# a2-display.net
KiCad netlist of a schematic drawn in EAGLE
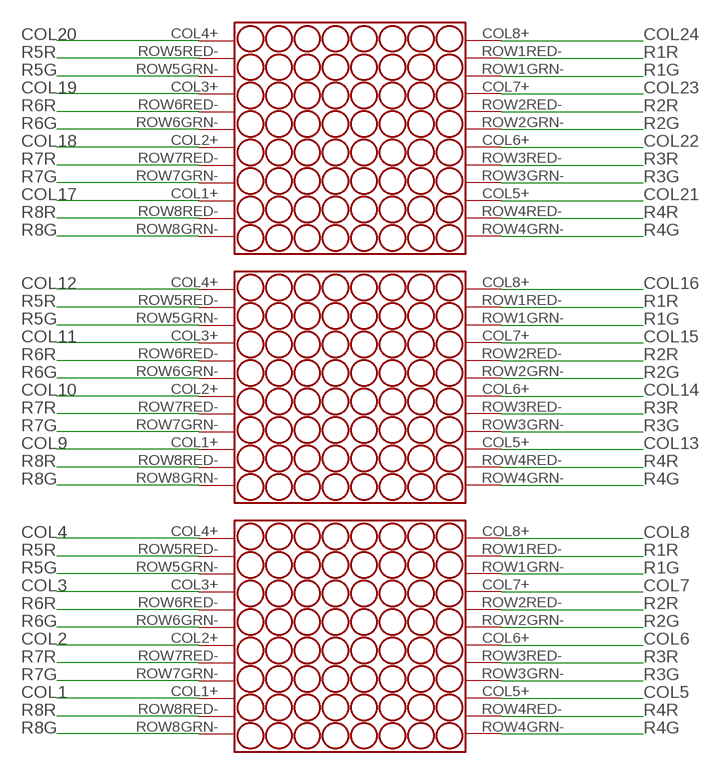
[diagram p0: schematic, sheet 1, part 1 of 2]
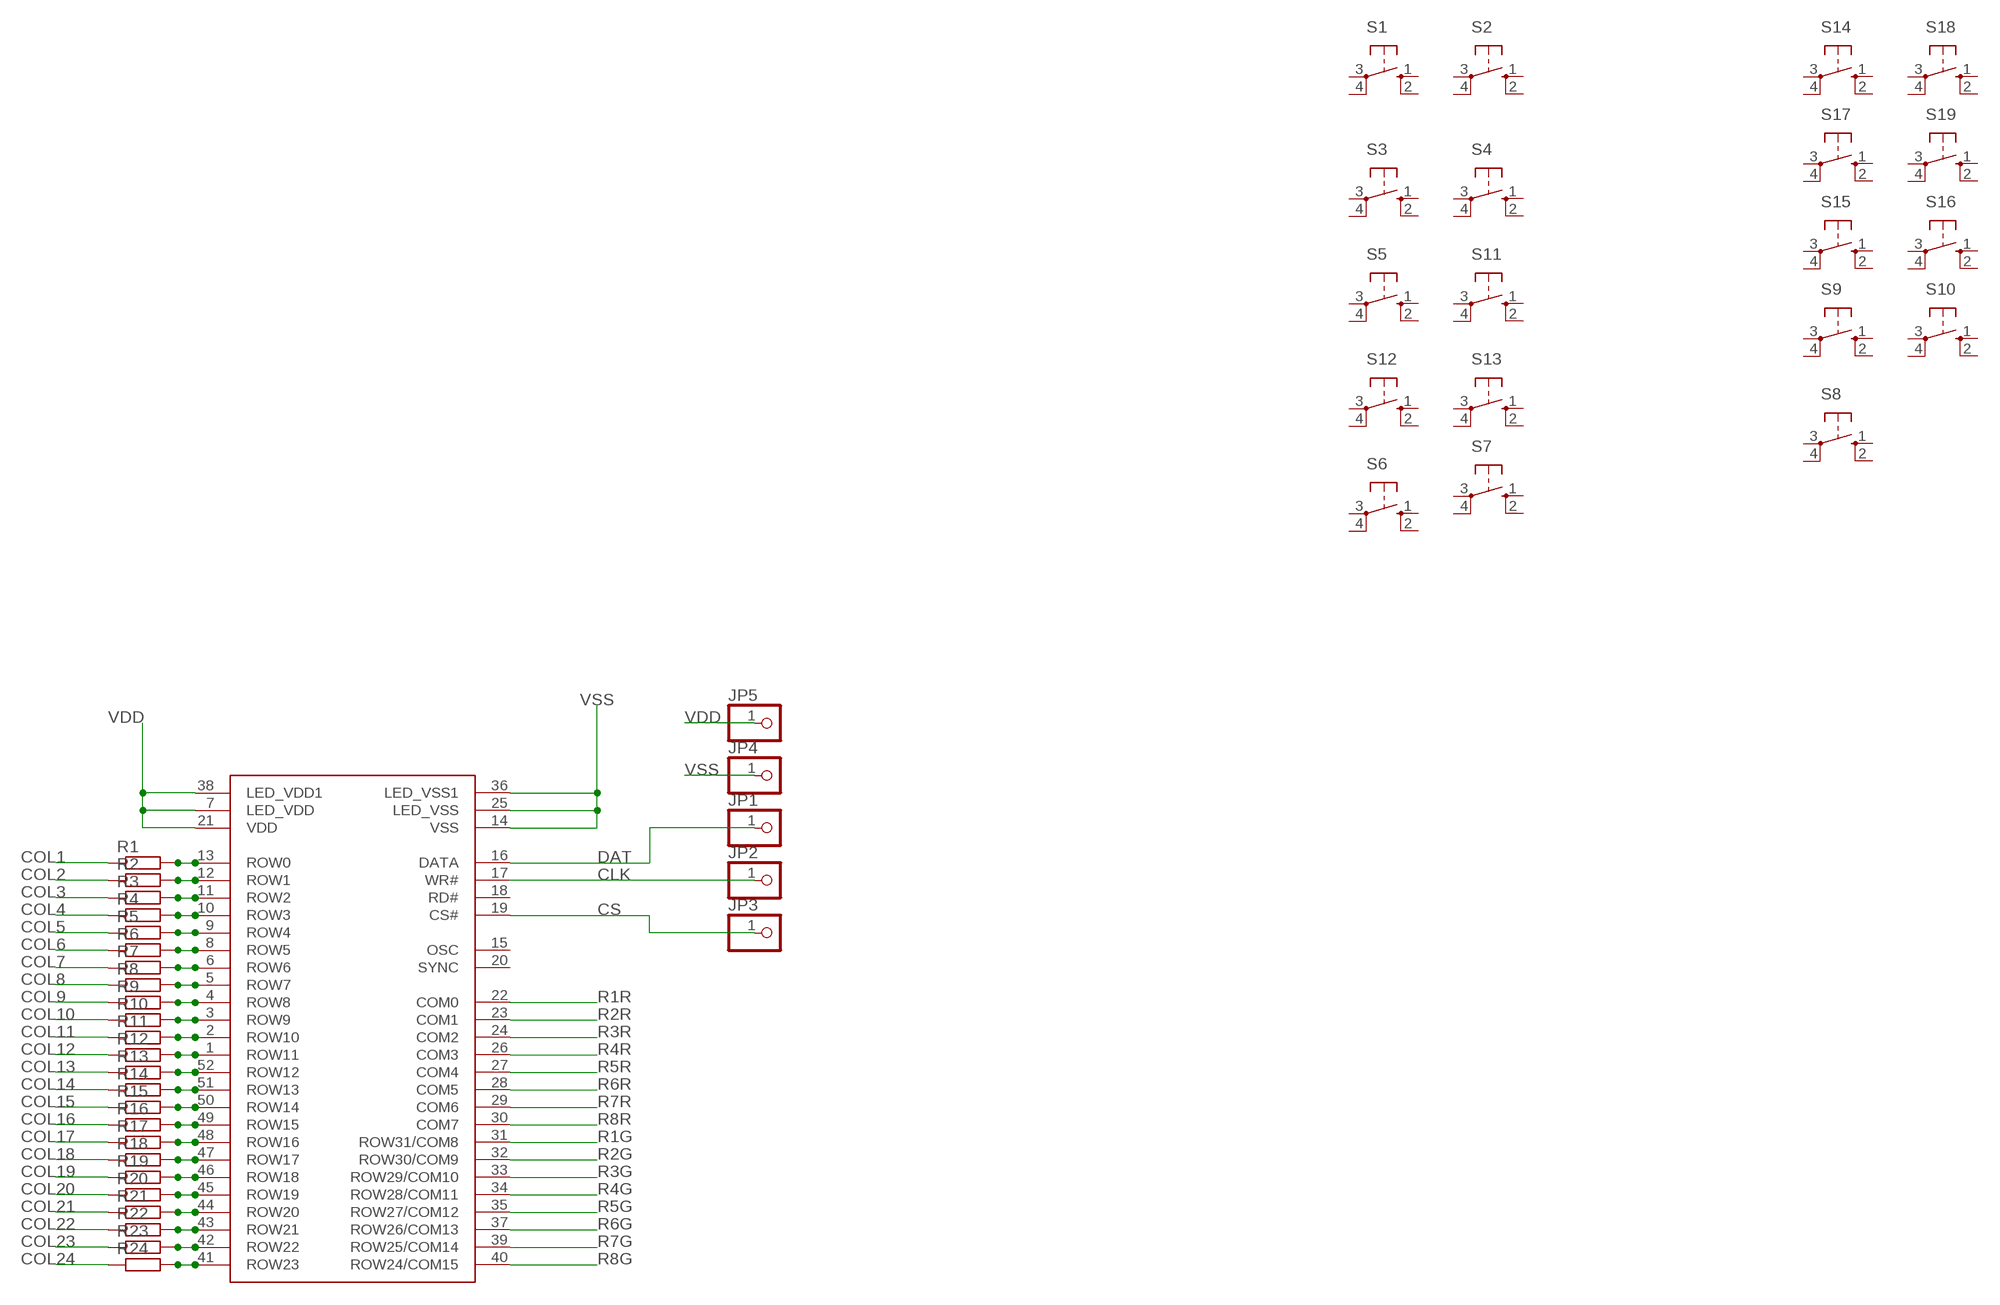
[diagram p1: schematic, sheet 1, part 2 of 2]

(export (version "E")
  (design (tool "Eeschema 10.0.6"))
  (components
    (comp (ref "IC1")
      (value "HT1632C")
      (footprint "eagle-import:QFP52")
      (libsource (lib "eagle-import") (part "HT1632C"))
    )
    (comp (ref "JP1")
      (value "PINHD-1X1")
      (footprint "eagle-import:1X01")
      (libsource (lib "eagle-import") (part "PINHD-1X1"))
    )
    (comp (ref "JP2")
      (value "PINHD-1X1")
      (footprint "eagle-import:1X01")
      (libsource (lib "eagle-import") (part "PINHD-1X1"))
    )
    (comp (ref "JP3")
      (value "PINHD-1X1")
      (footprint "eagle-import:1X01")
      (libsource (lib "eagle-import") (part "PINHD-1X1"))
    )
    (comp (ref "JP4")
      (value "PINHD-1X1")
      (footprint "eagle-import:1X01")
      (libsource (lib "eagle-import") (part "PINHD-1X1"))
    )
    (comp (ref "JP5")
      (value "PINHD-1X1")
      (footprint "eagle-import:1X01")
      (libsource (lib "eagle-import") (part "PINHD-1X1"))
    )
    (comp (ref "R1")
      (value "R-EU_R0805")
      (footprint "eagle-import:R0805")
      (libsource (lib "eagle-import") (part "R-EU_R0805"))
    )
    (comp (ref "R2")
      (value "R-EU_R0805")
      (footprint "eagle-import:R0805")
      (libsource (lib "eagle-import") (part "R-EU_R0805"))
    )
    (comp (ref "R3")
      (value "R-EU_R0805")
      (footprint "eagle-import:R0805")
      (libsource (lib "eagle-import") (part "R-EU_R0805"))
    )
    (comp (ref "R4")
      (value "R-EU_R0805")
      (footprint "eagle-import:R0805")
      (libsource (lib "eagle-import") (part "R-EU_R0805"))
    )
    (comp (ref "R5")
      (value "R-EU_R0805")
      (footprint "eagle-import:R0805")
      (libsource (lib "eagle-import") (part "R-EU_R0805"))
    )
    (comp (ref "R6")
      (value "R-EU_R0805")
      (footprint "eagle-import:R0805")
      (libsource (lib "eagle-import") (part "R-EU_R0805"))
    )
    (comp (ref "R7")
      (value "R-EU_R0805")
      (footprint "eagle-import:R0805")
      (libsource (lib "eagle-import") (part "R-EU_R0805"))
    )
    (comp (ref "R8")
      (value "R-EU_R0805")
      (footprint "eagle-import:R0805")
      (libsource (lib "eagle-import") (part "R-EU_R0805"))
    )
    (comp (ref "R9")
      (value "R-EU_R0805")
      (footprint "eagle-import:R0805")
      (libsource (lib "eagle-import") (part "R-EU_R0805"))
    )
    (comp (ref "R10")
      (value "R-EU_R0805")
      (footprint "eagle-import:R0805")
      (libsource (lib "eagle-import") (part "R-EU_R0805"))
    )
    (comp (ref "R11")
      (value "R-EU_R0805")
      (footprint "eagle-import:R0805")
      (libsource (lib "eagle-import") (part "R-EU_R0805"))
    )
    (comp (ref "R12")
      (value "R-EU_R0805")
      (footprint "eagle-import:R0805")
      (libsource (lib "eagle-import") (part "R-EU_R0805"))
    )
    (comp (ref "R13")
      (value "R-EU_R0805")
      (footprint "eagle-import:R0805")
      (libsource (lib "eagle-import") (part "R-EU_R0805"))
    )
    (comp (ref "R14")
      (value "R-EU_R0805")
      (footprint "eagle-import:R0805")
      (libsource (lib "eagle-import") (part "R-EU_R0805"))
    )
    (comp (ref "R15")
      (value "R-EU_R0805")
      (footprint "eagle-import:R0805")
      (libsource (lib "eagle-import") (part "R-EU_R0805"))
    )
    (comp (ref "R16")
      (value "R-EU_R0805")
      (footprint "eagle-import:R0805")
      (libsource (lib "eagle-import") (part "R-EU_R0805"))
    )
    (comp (ref "R17")
      (value "R-EU_R0805")
      (footprint "eagle-import:R0805")
      (libsource (lib "eagle-import") (part "R-EU_R0805"))
    )
    (comp (ref "R18")
      (value "R-EU_R0805")
      (footprint "eagle-import:R0805")
      (libsource (lib "eagle-import") (part "R-EU_R0805"))
    )
    (comp (ref "R19")
      (value "R-EU_R0805")
      (footprint "eagle-import:R0805")
      (libsource (lib "eagle-import") (part "R-EU_R0805"))
    )
    (comp (ref "R20")
      (value "R-EU_R0805")
      (footprint "eagle-import:R0805")
      (libsource (lib "eagle-import") (part "R-EU_R0805"))
    )
    (comp (ref "R21")
      (value "R-EU_R0805")
      (footprint "eagle-import:R0805")
      (libsource (lib "eagle-import") (part "R-EU_R0805"))
    )
    (comp (ref "R22")
      (value "R-EU_R0805")
      (footprint "eagle-import:R0805")
      (libsource (lib "eagle-import") (part "R-EU_R0805"))
    )
    (comp (ref "R23")
      (value "R-EU_R0805")
      (footprint "eagle-import:R0805")
      (libsource (lib "eagle-import") (part "R-EU_R0805"))
    )
    (comp (ref "R24")
      (value "R-EU_R0805")
      (footprint "eagle-import:R0805")
      (libsource (lib "eagle-import") (part "R-EU_R0805"))
    )
    (comp (ref "S1")
      (value "10-XX")
      (footprint "eagle-import:B3F-10XX")
      (fields (field (name "MPN") "B3F-1000"))
      (libsource (lib "eagle-import") (part "10-XX"))
    )
    (comp (ref "S2")
      (value "10-XX")
      (footprint "eagle-import:B3F-10XX")
      (fields (field (name "MPN") "B3F-1000"))
      (libsource (lib "eagle-import") (part "10-XX"))
    )
    (comp (ref "S3")
      (value "10-XX")
      (footprint "eagle-import:B3F-10XX")
      (fields (field (name "MPN") "B3F-1000"))
      (libsource (lib "eagle-import") (part "10-XX"))
    )
    (comp (ref "S4")
      (value "10-XX")
      (footprint "eagle-import:B3F-10XX")
      (fields (field (name "MPN") "B3F-1000"))
      (libsource (lib "eagle-import") (part "10-XX"))
    )
    (comp (ref "S5")
      (value "10-XX")
      (footprint "eagle-import:B3F-10XX")
      (fields (field (name "MPN") "B3F-1000"))
      (libsource (lib "eagle-import") (part "10-XX"))
    )
    (comp (ref "S6")
      (value "10-XX")
      (footprint "eagle-import:B3F-10XX")
      (fields (field (name "MPN") "B3F-1000"))
      (libsource (lib "eagle-import") (part "10-XX"))
    )
    (comp (ref "S7")
      (value "10-XX")
      (footprint "eagle-import:B3F-10XX")
      (fields (field (name "MPN") "B3F-1000"))
      (libsource (lib "eagle-import") (part "10-XX"))
    )
    (comp (ref "S8")
      (value "10-XX")
      (footprint "eagle-import:B3F-10XX")
      (fields (field (name "MPN") "B3F-1000"))
      (libsource (lib "eagle-import") (part "10-XX"))
    )
    (comp (ref "S9")
      (value "10-XX")
      (footprint "eagle-import:B3F-10XX")
      (fields (field (name "MPN") "B3F-1000"))
      (libsource (lib "eagle-import") (part "10-XX"))
    )
    (comp (ref "S10")
      (value "10-XX")
      (footprint "eagle-import:B3F-10XX")
      (fields (field (name "MPN") "B3F-1000"))
      (libsource (lib "eagle-import") (part "10-XX"))
    )
    (comp (ref "S11")
      (value "10-XX")
      (footprint "eagle-import:B3F-10XX")
      (fields (field (name "MPN") "B3F-1000"))
      (libsource (lib "eagle-import") (part "10-XX"))
    )
    (comp (ref "S12")
      (value "10-XX")
      (footprint "eagle-import:B3F-10XX")
      (fields (field (name "MPN") "B3F-1000"))
      (libsource (lib "eagle-import") (part "10-XX"))
    )
    (comp (ref "S13")
      (value "10-XX")
      (footprint "eagle-import:B3F-10XX")
      (fields (field (name "MPN") "B3F-1000"))
      (libsource (lib "eagle-import") (part "10-XX"))
    )
    (comp (ref "S14")
      (value "10-XX")
      (footprint "eagle-import:B3F-10XX")
      (fields (field (name "MPN") "B3F-1000"))
      (libsource (lib "eagle-import") (part "10-XX"))
    )
    (comp (ref "S15")
      (value "10-XX")
      (footprint "eagle-import:B3F-10XX")
      (fields (field (name "MPN") "B3F-1000"))
      (libsource (lib "eagle-import") (part "10-XX"))
    )
    (comp (ref "S16")
      (value "10-XX")
      (footprint "eagle-import:B3F-10XX")
      (fields (field (name "MPN") "B3F-1000"))
      (libsource (lib "eagle-import") (part "10-XX"))
    )
    (comp (ref "S17")
      (value "10-XX")
      (footprint "eagle-import:B3F-10XX")
      (fields (field (name "MPN") "B3F-1000"))
      (libsource (lib "eagle-import") (part "10-XX"))
    )
    (comp (ref "S18")
      (value "10-XX")
      (footprint "eagle-import:B3F-10XX")
      (fields (field (name "MPN") "B3F-1000"))
      (libsource (lib "eagle-import") (part "10-XX"))
    )
    (comp (ref "S19")
      (value "10-XX")
      (footprint "eagle-import:B3F-10XX")
      (fields (field (name "MPN") "B3F-1000"))
      (libsource (lib "eagle-import") (part "10-XX"))
    )
    (comp (ref "U$1")
      (value "8X8")
      (footprint "eagle-import:SURE8X8")
      (libsource (lib "eagle-import") (part "8X8"))
    )
    (comp (ref "U$2")
      (value "8X8")
      (footprint "eagle-import:SURE8X8")
      (libsource (lib "eagle-import") (part "8X8"))
    )
    (comp (ref "U$3")
      (value "8X8")
      (footprint "eagle-import:SURE8X8")
      (libsource (lib "eagle-import") (part "8X8"))
    )
  )
  (nets
    (net (code "1") (name "/CLK") (class "Default")
      (node (ref "IC1") (pin "17") (pinfunction "WR#_17") (pintype "bidirectional"))
      (node (ref "JP2") (pin "1") (pinfunction "1_1") (pintype "passive"))
    )
    (net (code "2") (name "/COL1") (class "Default")
      (node (ref "R1") (pin "1") (pinfunction "1_1") (pintype "passive"))
      (node (ref "U$3") (pin "COL1+") (pinfunction "COL1_AN_COL1+") (pintype "passive"))
    )
    (net (code "3") (name "/COL2") (class "Default")
      (node (ref "R2") (pin "1") (pinfunction "1_1") (pintype "passive"))
      (node (ref "U$3") (pin "COL2+") (pinfunction "COL2_AN_COL2+") (pintype "passive"))
    )
    (net (code "4") (name "/COL3") (class "Default")
      (node (ref "R3") (pin "1") (pinfunction "1_1") (pintype "passive"))
      (node (ref "U$3") (pin "COL3+") (pinfunction "COL3_AN_COL3+") (pintype "passive"))
    )
    (net (code "5") (name "/COL4") (class "Default")
      (node (ref "R4") (pin "1") (pinfunction "1_1") (pintype "passive"))
      (node (ref "U$3") (pin "COL4+") (pinfunction "COL4_AN_COL4+") (pintype "passive"))
    )
    (net (code "6") (name "/COL5") (class "Default")
      (node (ref "R5") (pin "1") (pinfunction "1_1") (pintype "passive"))
      (node (ref "U$3") (pin "COL5+") (pinfunction "COL5_AN_COL5+") (pintype "passive"))
    )
    (net (code "7") (name "/COL6") (class "Default")
      (node (ref "R6") (pin "1") (pinfunction "1_1") (pintype "passive"))
      (node (ref "U$3") (pin "COL6+") (pinfunction "COL6_AN_COL6+") (pintype "passive"))
    )
    (net (code "8") (name "/COL7") (class "Default")
      (node (ref "R7") (pin "1") (pinfunction "1_1") (pintype "passive"))
      (node (ref "U$3") (pin "COL7+") (pinfunction "COL7_AN_COL7+") (pintype "passive"))
    )
    (net (code "9") (name "/COL8") (class "Default")
      (node (ref "R8") (pin "1") (pinfunction "1_1") (pintype "passive"))
      (node (ref "U$3") (pin "COL8+") (pinfunction "COL8_AN_COL8+") (pintype "passive"))
    )
    (net (code "10") (name "/COL9") (class "Default")
      (node (ref "R9") (pin "1") (pinfunction "1_1") (pintype "passive"))
      (node (ref "U$2") (pin "COL1+") (pinfunction "COL1_AN_COL1+") (pintype "passive"))
    )
    (net (code "11") (name "/COL10") (class "Default")
      (node (ref "R10") (pin "1") (pinfunction "1_1") (pintype "passive"))
      (node (ref "U$2") (pin "COL2+") (pinfunction "COL2_AN_COL2+") (pintype "passive"))
    )
    (net (code "12") (name "/COL11") (class "Default")
      (node (ref "R11") (pin "1") (pinfunction "1_1") (pintype "passive"))
      (node (ref "U$2") (pin "COL3+") (pinfunction "COL3_AN_COL3+") (pintype "passive"))
    )
    (net (code "13") (name "/COL12") (class "Default")
      (node (ref "R12") (pin "1") (pinfunction "1_1") (pintype "passive"))
      (node (ref "U$2") (pin "COL4+") (pinfunction "COL4_AN_COL4+") (pintype "passive"))
    )
    (net (code "14") (name "/COL13") (class "Default")
      (node (ref "R13") (pin "1") (pinfunction "1_1") (pintype "passive"))
      (node (ref "U$2") (pin "COL5+") (pinfunction "COL5_AN_COL5+") (pintype "passive"))
    )
    (net (code "15") (name "/COL14") (class "Default")
      (node (ref "R14") (pin "1") (pinfunction "1_1") (pintype "passive"))
      (node (ref "U$2") (pin "COL6+") (pinfunction "COL6_AN_COL6+") (pintype "passive"))
    )
    (net (code "16") (name "/COL15") (class "Default")
      (node (ref "R15") (pin "1") (pinfunction "1_1") (pintype "passive"))
      (node (ref "U$2") (pin "COL7+") (pinfunction "COL7_AN_COL7+") (pintype "passive"))
    )
    (net (code "17") (name "/COL16") (class "Default")
      (node (ref "R16") (pin "1") (pinfunction "1_1") (pintype "passive"))
      (node (ref "U$2") (pin "COL8+") (pinfunction "COL8_AN_COL8+") (pintype "passive"))
    )
    (net (code "18") (name "/COL17") (class "Default")
      (node (ref "R17") (pin "1") (pinfunction "1_1") (pintype "passive"))
      (node (ref "U$1") (pin "COL1+") (pinfunction "COL1_AN_COL1+") (pintype "passive"))
    )
    (net (code "19") (name "/COL18") (class "Default")
      (node (ref "R18") (pin "1") (pinfunction "1_1") (pintype "passive"))
      (node (ref "U$1") (pin "COL2+") (pinfunction "COL2_AN_COL2+") (pintype "passive"))
    )
    (net (code "20") (name "/COL19") (class "Default")
      (node (ref "R19") (pin "1") (pinfunction "1_1") (pintype "passive"))
      (node (ref "U$1") (pin "COL3+") (pinfunction "COL3_AN_COL3+") (pintype "passive"))
    )
    (net (code "21") (name "/COL20") (class "Default")
      (node (ref "R20") (pin "1") (pinfunction "1_1") (pintype "passive"))
      (node (ref "U$1") (pin "COL4+") (pinfunction "COL4_AN_COL4+") (pintype "passive"))
    )
    (net (code "22") (name "/COL21") (class "Default")
      (node (ref "R21") (pin "1") (pinfunction "1_1") (pintype "passive"))
      (node (ref "U$1") (pin "COL5+") (pinfunction "COL5_AN_COL5+") (pintype "passive"))
    )
    (net (code "23") (name "/COL22") (class "Default")
      (node (ref "R22") (pin "1") (pinfunction "1_1") (pintype "passive"))
      (node (ref "U$1") (pin "COL6+") (pinfunction "COL6_AN_COL6+") (pintype "passive"))
    )
    (net (code "24") (name "/COL23") (class "Default")
      (node (ref "R23") (pin "1") (pinfunction "1_1") (pintype "passive"))
      (node (ref "U$1") (pin "COL7+") (pinfunction "COL7_AN_COL7+") (pintype "passive"))
    )
    (net (code "25") (name "/COL24") (class "Default")
      (node (ref "R24") (pin "1") (pinfunction "1_1") (pintype "passive"))
      (node (ref "U$1") (pin "COL8+") (pinfunction "COL8_AN_COL8+") (pintype "passive"))
    )
    (net (code "26") (name "/CS") (class "Default")
      (node (ref "IC1") (pin "19") (pinfunction "CS#_19") (pintype "bidirectional"))
      (node (ref "JP3") (pin "1") (pinfunction "1_1") (pintype "passive"))
    )
    (net (code "27") (name "/DAT") (class "Default")
      (node (ref "IC1") (pin "16") (pinfunction "DATA_16") (pintype "bidirectional"))
      (node (ref "JP1") (pin "1") (pinfunction "1_1") (pintype "passive"))
    )
    (net (code "28") (name "/R1G") (class "Default")
      (node (ref "IC1") (pin "31") (pinfunction "ROW31/COM8_31") (pintype "bidirectional"))
      (node (ref "U$1") (pin "ROW1GRN-") (pinfunction "GRN1_CA_ROW1GRN-") (pintype "passive"))
      (node (ref "U$2") (pin "ROW1GRN-") (pinfunction "GRN1_CA_ROW1GRN-") (pintype "passive"))
      (node (ref "U$3") (pin "ROW1GRN-") (pinfunction "GRN1_CA_ROW1GRN-") (pintype "passive"))
    )
    (net (code "29") (name "/R1R") (class "Default")
      (node (ref "IC1") (pin "22") (pinfunction "COM0_22") (pintype "bidirectional"))
      (node (ref "U$1") (pin "ROW1RED-") (pinfunction "RED1_CA_ROW1RED-") (pintype "passive"))
      (node (ref "U$2") (pin "ROW1RED-") (pinfunction "RED1_CA_ROW1RED-") (pintype "passive"))
      (node (ref "U$3") (pin "ROW1RED-") (pinfunction "RED1_CA_ROW1RED-") (pintype "passive"))
    )
    (net (code "30") (name "/R2G") (class "Default")
      (node (ref "IC1") (pin "32") (pinfunction "ROW30/COM9_32") (pintype "bidirectional"))
      (node (ref "U$1") (pin "ROW2GRN-") (pinfunction "GRN2_CA_ROW2GRN-") (pintype "passive"))
      (node (ref "U$2") (pin "ROW2GRN-") (pinfunction "GRN2_CA_ROW2GRN-") (pintype "passive"))
      (node (ref "U$3") (pin "ROW2GRN-") (pinfunction "GRN2_CA_ROW2GRN-") (pintype "passive"))
    )
    (net (code "31") (name "/R2R") (class "Default")
      (node (ref "IC1") (pin "23") (pinfunction "COM1_23") (pintype "bidirectional"))
      (node (ref "U$1") (pin "ROW2RED-") (pinfunction "RED2_CA_ROW2RED-") (pintype "passive"))
      (node (ref "U$2") (pin "ROW2RED-") (pinfunction "RED2_CA_ROW2RED-") (pintype "passive"))
      (node (ref "U$3") (pin "ROW2RED-") (pinfunction "RED2_CA_ROW2RED-") (pintype "passive"))
    )
    (net (code "32") (name "/R3G") (class "Default")
      (node (ref "IC1") (pin "33") (pinfunction "ROW29/COM10_33") (pintype "bidirectional"))
      (node (ref "U$1") (pin "ROW3GRN-") (pinfunction "GRN3_CA_ROW3GRN-") (pintype "passive"))
      (node (ref "U$2") (pin "ROW3GRN-") (pinfunction "GRN3_CA_ROW3GRN-") (pintype "passive"))
      (node (ref "U$3") (pin "ROW3GRN-") (pinfunction "GRN3_CA_ROW3GRN-") (pintype "passive"))
    )
    (net (code "33") (name "/R3R") (class "Default")
      (node (ref "IC1") (pin "24") (pinfunction "COM2_24") (pintype "bidirectional"))
      (node (ref "U$1") (pin "ROW3RED-") (pinfunction "RED3_CA_ROW3RED-") (pintype "passive"))
      (node (ref "U$2") (pin "ROW3RED-") (pinfunction "RED3_CA_ROW3RED-") (pintype "passive"))
      (node (ref "U$3") (pin "ROW3RED-") (pinfunction "RED3_CA_ROW3RED-") (pintype "passive"))
    )
    (net (code "34") (name "/R4G") (class "Default")
      (node (ref "IC1") (pin "34") (pinfunction "ROW28/COM11_34") (pintype "bidirectional"))
      (node (ref "U$1") (pin "ROW4GRN-") (pinfunction "GRN4_CA_ROW4GRN-") (pintype "passive"))
      (node (ref "U$2") (pin "ROW4GRN-") (pinfunction "GRN4_CA_ROW4GRN-") (pintype "passive"))
      (node (ref "U$3") (pin "ROW4GRN-") (pinfunction "GRN4_CA_ROW4GRN-") (pintype "passive"))
    )
    (net (code "35") (name "/R4R") (class "Default")
      (node (ref "IC1") (pin "26") (pinfunction "COM3_26") (pintype "bidirectional"))
      (node (ref "U$1") (pin "ROW4RED-") (pinfunction "RED4_CA_ROW4RED-") (pintype "passive"))
      (node (ref "U$2") (pin "ROW4RED-") (pinfunction "RED4_CA_ROW4RED-") (pintype "passive"))
      (node (ref "U$3") (pin "ROW4RED-") (pinfunction "RED4_CA_ROW4RED-") (pintype "passive"))
    )
    (net (code "36") (name "/R5G") (class "Default")
      (node (ref "IC1") (pin "35") (pinfunction "ROW27/COM12_35") (pintype "bidirectional"))
      (node (ref "U$1") (pin "ROW5GRN-") (pinfunction "GRN5_CA_ROW5GRN-") (pintype "passive"))
      (node (ref "U$2") (pin "ROW5GRN-") (pinfunction "GRN5_CA_ROW5GRN-") (pintype "passive"))
      (node (ref "U$3") (pin "ROW5GRN-") (pinfunction "GRN5_CA_ROW5GRN-") (pintype "passive"))
    )
    (net (code "37") (name "/R5R") (class "Default")
      (node (ref "IC1") (pin "27") (pinfunction "COM4_27") (pintype "bidirectional"))
      (node (ref "U$1") (pin "ROW5RED-") (pinfunction "RED5_CA_ROW5RED-") (pintype "passive"))
      (node (ref "U$2") (pin "ROW5RED-") (pinfunction "RED5_CA_ROW5RED-") (pintype "passive"))
      (node (ref "U$3") (pin "ROW5RED-") (pinfunction "RED5_CA_ROW5RED-") (pintype "passive"))
    )
    (net (code "38") (name "/R6G") (class "Default")
      (node (ref "IC1") (pin "37") (pinfunction "ROW26/COM13_37") (pintype "bidirectional"))
      (node (ref "U$1") (pin "ROW6GRN-") (pinfunction "GRN6_CA_ROW6GRN-") (pintype "passive"))
      (node (ref "U$2") (pin "ROW6GRN-") (pinfunction "GRN6_CA_ROW6GRN-") (pintype "passive"))
      (node (ref "U$3") (pin "ROW6GRN-") (pinfunction "GRN6_CA_ROW6GRN-") (pintype "passive"))
    )
    (net (code "39") (name "/R6R") (class "Default")
      (node (ref "IC1") (pin "28") (pinfunction "COM5_28") (pintype "bidirectional"))
      (node (ref "U$1") (pin "ROW6RED-") (pinfunction "RED6_CA_ROW6RED-") (pintype "passive"))
      (node (ref "U$2") (pin "ROW6RED-") (pinfunction "RED6_CA_ROW6RED-") (pintype "passive"))
      (node (ref "U$3") (pin "ROW6RED-") (pinfunction "RED6_CA_ROW6RED-") (pintype "passive"))
    )
    (net (code "40") (name "/R7G") (class "Default")
      (node (ref "IC1") (pin "39") (pinfunction "ROW25/COM14_39") (pintype "bidirectional"))
      (node (ref "U$1") (pin "ROW7GRN-") (pinfunction "GRN7_CA_ROW7GRN-") (pintype "passive"))
      (node (ref "U$2") (pin "ROW7GRN-") (pinfunction "GRN7_CA_ROW7GRN-") (pintype "passive"))
      (node (ref "U$3") (pin "ROW7GRN-") (pinfunction "GRN7_CA_ROW7GRN-") (pintype "passive"))
    )
    (net (code "41") (name "/R7R") (class "Default")
      (node (ref "IC1") (pin "29") (pinfunction "COM6_29") (pintype "bidirectional"))
      (node (ref "U$1") (pin "ROW7RED-") (pinfunction "RED7_CA_ROW7RED-") (pintype "passive"))
      (node (ref "U$2") (pin "ROW7RED-") (pinfunction "RED7_CA_ROW7RED-") (pintype "passive"))
      (node (ref "U$3") (pin "ROW7RED-") (pinfunction "RED7_CA_ROW7RED-") (pintype "passive"))
    )
    (net (code "42") (name "/R8G") (class "Default")
      (node (ref "IC1") (pin "40") (pinfunction "ROW24/COM15_40") (pintype "bidirectional"))
      (node (ref "U$1") (pin "ROW8GRN-") (pinfunction "GRN8_CA_ROW8GRN-") (pintype "passive"))
      (node (ref "U$2") (pin "ROW8GRN-") (pinfunction "GRN8_CA_ROW8GRN-") (pintype "passive"))
      (node (ref "U$3") (pin "ROW8GRN-") (pinfunction "GRN8_CA_ROW8GRN-") (pintype "passive"))
    )
    (net (code "43") (name "/R8R") (class "Default")
      (node (ref "IC1") (pin "30") (pinfunction "COM7_30") (pintype "bidirectional"))
      (node (ref "U$1") (pin "ROW8RED-") (pinfunction "RED8_CA_ROW8RED-") (pintype "passive"))
      (node (ref "U$2") (pin "ROW8RED-") (pinfunction "RED8_CA_ROW8RED-") (pintype "passive"))
      (node (ref "U$3") (pin "ROW8RED-") (pinfunction "RED8_CA_ROW8RED-") (pintype "passive"))
    )
    (net (code "44") (name "/VDD") (class "Default")
      (node (ref "IC1") (pin "21") (pinfunction "VDD_21") (pintype "bidirectional"))
      (node (ref "IC1") (pin "38") (pinfunction "LED_VDD1_38") (pintype "bidirectional"))
      (node (ref "IC1") (pin "7") (pinfunction "LED_VDD_7") (pintype "bidirectional"))
      (node (ref "JP5") (pin "1") (pinfunction "1_1") (pintype "passive"))
    )
    (net (code "45") (name "/VSS") (class "Default")
      (node (ref "IC1") (pin "14") (pinfunction "VSS_14") (pintype "bidirectional"))
      (node (ref "IC1") (pin "25") (pinfunction "LED_VSS_25") (pintype "bidirectional"))
      (node (ref "IC1") (pin "36") (pinfunction "LED_VSS1_36") (pintype "bidirectional"))
      (node (ref "JP4") (pin "1") (pinfunction "1_1") (pintype "passive"))
    )
    (net (code "46") (name "Net-(IC1-ROW0)") (class "Default")
      (node (ref "IC1") (pin "13") (pinfunction "ROW0_13") (pintype "bidirectional"))
      (node (ref "R1") (pin "2") (pinfunction "2_2") (pintype "passive"))
    )
    (net (code "47") (name "Net-(IC1-ROW1)") (class "Default")
      (node (ref "IC1") (pin "12") (pinfunction "ROW1_12") (pintype "bidirectional"))
      (node (ref "R2") (pin "2") (pinfunction "2_2") (pintype "passive"))
    )
    (net (code "48") (name "Net-(IC1-ROW2)") (class "Default")
      (node (ref "IC1") (pin "11") (pinfunction "ROW2_11") (pintype "bidirectional"))
      (node (ref "R3") (pin "2") (pinfunction "2_2") (pintype "passive"))
    )
    (net (code "49") (name "Net-(IC1-ROW3)") (class "Default")
      (node (ref "IC1") (pin "10") (pinfunction "ROW3_10") (pintype "bidirectional"))
      (node (ref "R4") (pin "2") (pinfunction "2_2") (pintype "passive"))
    )
    (net (code "50") (name "Net-(IC1-ROW4)") (class "Default")
      (node (ref "IC1") (pin "9") (pinfunction "ROW4_9") (pintype "bidirectional"))
      (node (ref "R5") (pin "2") (pinfunction "2_2") (pintype "passive"))
    )
    (net (code "51") (name "Net-(IC1-ROW5)") (class "Default")
      (node (ref "IC1") (pin "8") (pinfunction "ROW5_8") (pintype "bidirectional"))
      (node (ref "R6") (pin "2") (pinfunction "2_2") (pintype "passive"))
    )
    (net (code "52") (name "Net-(IC1-ROW6)") (class "Default")
      (node (ref "IC1") (pin "6") (pinfunction "ROW6_6") (pintype "bidirectional"))
      (node (ref "R7") (pin "2") (pinfunction "2_2") (pintype "passive"))
    )
    (net (code "53") (name "Net-(IC1-ROW7)") (class "Default")
      (node (ref "IC1") (pin "5") (pinfunction "ROW7_5") (pintype "bidirectional"))
      (node (ref "R8") (pin "2") (pinfunction "2_2") (pintype "passive"))
    )
    (net (code "54") (name "Net-(IC1-ROW8)") (class "Default")
      (node (ref "IC1") (pin "4") (pinfunction "ROW8_4") (pintype "bidirectional"))
      (node (ref "R9") (pin "2") (pinfunction "2_2") (pintype "passive"))
    )
    (net (code "55") (name "Net-(IC1-ROW9)") (class "Default")
      (node (ref "IC1") (pin "3") (pinfunction "ROW9_3") (pintype "bidirectional"))
      (node (ref "R10") (pin "2") (pinfunction "2_2") (pintype "passive"))
    )
    (net (code "56") (name "Net-(IC1-ROW10)") (class "Default")
      (node (ref "IC1") (pin "2") (pinfunction "ROW10_2") (pintype "bidirectional"))
      (node (ref "R11") (pin "2") (pinfunction "2_2") (pintype "passive"))
    )
    (net (code "57") (name "Net-(IC1-ROW11)") (class "Default")
      (node (ref "IC1") (pin "1") (pinfunction "ROW11_1") (pintype "bidirectional"))
      (node (ref "R12") (pin "2") (pinfunction "2_2") (pintype "passive"))
    )
    (net (code "58") (name "Net-(IC1-ROW12)") (class "Default")
      (node (ref "IC1") (pin "52") (pinfunction "ROW12_52") (pintype "bidirectional"))
      (node (ref "R13") (pin "2") (pinfunction "2_2") (pintype "passive"))
    )
    (net (code "59") (name "Net-(IC1-ROW13)") (class "Default")
      (node (ref "IC1") (pin "51") (pinfunction "ROW13_51") (pintype "bidirectional"))
      (node (ref "R14") (pin "2") (pinfunction "2_2") (pintype "passive"))
    )
    (net (code "60") (name "Net-(IC1-ROW14)") (class "Default")
      (node (ref "IC1") (pin "50") (pinfunction "ROW14_50") (pintype "bidirectional"))
      (node (ref "R15") (pin "2") (pinfunction "2_2") (pintype "passive"))
    )
    (net (code "61") (name "Net-(IC1-ROW15)") (class "Default")
      (node (ref "IC1") (pin "49") (pinfunction "ROW15_49") (pintype "bidirectional"))
      (node (ref "R16") (pin "2") (pinfunction "2_2") (pintype "passive"))
    )
    (net (code "62") (name "Net-(IC1-ROW16)") (class "Default")
      (node (ref "IC1") (pin "48") (pinfunction "ROW16_48") (pintype "bidirectional"))
      (node (ref "R17") (pin "2") (pinfunction "2_2") (pintype "passive"))
    )
    (net (code "63") (name "Net-(IC1-ROW17)") (class "Default")
      (node (ref "IC1") (pin "47") (pinfunction "ROW17_47") (pintype "bidirectional"))
      (node (ref "R18") (pin "2") (pinfunction "2_2") (pintype "passive"))
    )
    (net (code "64") (name "Net-(IC1-ROW18)") (class "Default")
      (node (ref "IC1") (pin "46") (pinfunction "ROW18_46") (pintype "bidirectional"))
      (node (ref "R19") (pin "2") (pinfunction "2_2") (pintype "passive"))
    )
    (net (code "65") (name "Net-(IC1-ROW19)") (class "Default")
      (node (ref "IC1") (pin "45") (pinfunction "ROW19_45") (pintype "bidirectional"))
      (node (ref "R20") (pin "2") (pinfunction "2_2") (pintype "passive"))
    )
    (net (code "66") (name "Net-(IC1-ROW20)") (class "Default")
      (node (ref "IC1") (pin "44") (pinfunction "ROW20_44") (pintype "bidirectional"))
      (node (ref "R21") (pin "2") (pinfunction "2_2") (pintype "passive"))
    )
    (net (code "67") (name "Net-(IC1-ROW21)") (class "Default")
      (node (ref "IC1") (pin "43") (pinfunction "ROW21_43") (pintype "bidirectional"))
      (node (ref "R22") (pin "2") (pinfunction "2_2") (pintype "passive"))
    )
    (net (code "68") (name "Net-(IC1-ROW22)") (class "Default")
      (node (ref "IC1") (pin "42") (pinfunction "ROW22_42") (pintype "bidirectional"))
      (node (ref "R23") (pin "2") (pinfunction "2_2") (pintype "passive"))
    )
    (net (code "69") (name "Net-(IC1-ROW23)") (class "Default")
      (node (ref "IC1") (pin "41") (pinfunction "ROW23_41") (pintype "bidirectional"))
      (node (ref "R24") (pin "2") (pinfunction "2_2") (pintype "passive"))
    )
    (net (code "70") (name "unconnected-(IC1-OSC-Pad15)") (class "Default")
      (node (ref "IC1") (pin "15") (pinfunction "OSC_15") (pintype "bidirectional"))
    )
    (net (code "71") (name "unconnected-(IC1-RD#-Pad18)") (class "Default")
      (node (ref "IC1") (pin "18") (pinfunction "RD#_18") (pintype "bidirectional"))
    )
    (net (code "72") (name "unconnected-(IC1-SYNC-Pad20)") (class "Default")
      (node (ref "IC1") (pin "20") (pinfunction "SYNC_20") (pintype "bidirectional"))
    )
    (net (code "73") (name "unconnected-(S1-P-Pad3)") (class "Default")
      (node (ref "S1") (pin "3") (pinfunction "P_3") (pintype "passive"))
    )
    (net (code "74") (name "unconnected-(S1-P1-Pad4)") (class "Default")
      (node (ref "S1") (pin "4") (pinfunction "P1_4") (pintype "passive"))
    )
    (net (code "75") (name "unconnected-(S1-S-Pad1)") (class "Default")
      (node (ref "S1") (pin "1") (pinfunction "S_1") (pintype "passive"))
    )
    (net (code "76") (name "unconnected-(S1-S1-Pad2)") (class "Default")
      (node (ref "S1") (pin "2") (pinfunction "S1_2") (pintype "passive"))
    )
    (net (code "77") (name "unconnected-(S2-P-Pad3)") (class "Default")
      (node (ref "S2") (pin "3") (pinfunction "P_3") (pintype "passive"))
    )
    (net (code "78") (name "unconnected-(S2-P1-Pad4)") (class "Default")
      (node (ref "S2") (pin "4") (pinfunction "P1_4") (pintype "passive"))
    )
    (net (code "79") (name "unconnected-(S2-S-Pad1)") (class "Default")
      (node (ref "S2") (pin "1") (pinfunction "S_1") (pintype "passive"))
    )
    (net (code "80") (name "unconnected-(S2-S1-Pad2)") (class "Default")
      (node (ref "S2") (pin "2") (pinfunction "S1_2") (pintype "passive"))
    )
    (net (code "81") (name "unconnected-(S3-P-Pad3)") (class "Default")
      (node (ref "S3") (pin "3") (pinfunction "P_3") (pintype "passive"))
    )
    (net (code "82") (name "unconnected-(S3-P1-Pad4)") (class "Default")
      (node (ref "S3") (pin "4") (pinfunction "P1_4") (pintype "passive"))
    )
    (net (code "83") (name "unconnected-(S3-S-Pad1)") (class "Default")
      (node (ref "S3") (pin "1") (pinfunction "S_1") (pintype "passive"))
    )
    (net (code "84") (name "unconnected-(S3-S1-Pad2)") (class "Default")
      (node (ref "S3") (pin "2") (pinfunction "S1_2") (pintype "passive"))
    )
    (net (code "85") (name "unconnected-(S4-P-Pad3)") (class "Default")
      (node (ref "S4") (pin "3") (pinfunction "P_3") (pintype "passive"))
    )
    (net (code "86") (name "unconnected-(S4-P1-Pad4)") (class "Default")
      (node (ref "S4") (pin "4") (pinfunction "P1_4") (pintype "passive"))
    )
    (net (code "87") (name "unconnected-(S4-S-Pad1)") (class "Default")
      (node (ref "S4") (pin "1") (pinfunction "S_1") (pintype "passive"))
    )
    (net (code "88") (name "unconnected-(S4-S1-Pad2)") (class "Default")
      (node (ref "S4") (pin "2") (pinfunction "S1_2") (pintype "passive"))
    )
    (net (code "89") (name "unconnected-(S5-P-Pad3)") (class "Default")
      (node (ref "S5") (pin "3") (pinfunction "P_3") (pintype "passive"))
    )
    (net (code "90") (name "unconnected-(S5-P1-Pad4)") (class "Default")
      (node (ref "S5") (pin "4") (pinfunction "P1_4") (pintype "passive"))
    )
    (net (code "91") (name "unconnected-(S5-S-Pad1)") (class "Default")
      (node (ref "S5") (pin "1") (pinfunction "S_1") (pintype "passive"))
    )
    (net (code "92") (name "unconnected-(S5-S1-Pad2)") (class "Default")
      (node (ref "S5") (pin "2") (pinfunction "S1_2") (pintype "passive"))
    )
    (net (code "93") (name "unconnected-(S6-P-Pad3)") (class "Default")
      (node (ref "S6") (pin "3") (pinfunction "P_3") (pintype "passive"))
    )
    (net (code "94") (name "unconnected-(S6-P1-Pad4)") (class "Default")
      (node (ref "S6") (pin "4") (pinfunction "P1_4") (pintype "passive"))
    )
    (net (code "95") (name "unconnected-(S6-S-Pad1)") (class "Default")
      (node (ref "S6") (pin "1") (pinfunction "S_1") (pintype "passive"))
    )
    (net (code "96") (name "unconnected-(S6-S1-Pad2)") (class "Default")
      (node (ref "S6") (pin "2") (pinfunction "S1_2") (pintype "passive"))
    )
    (net (code "97") (name "unconnected-(S7-P-Pad3)") (class "Default")
      (node (ref "S7") (pin "3") (pinfunction "P_3") (pintype "passive"))
    )
    (net (code "98") (name "unconnected-(S7-P1-Pad4)") (class "Default")
      (node (ref "S7") (pin "4") (pinfunction "P1_4") (pintype "passive"))
    )
    (net (code "99") (name "unconnected-(S7-S-Pad1)") (class "Default")
      (node (ref "S7") (pin "1") (pinfunction "S_1") (pintype "passive"))
    )
    (net (code "100") (name "unconnected-(S7-S1-Pad2)") (class "Default")
      (node (ref "S7") (pin "2") (pinfunction "S1_2") (pintype "passive"))
    )
    (net (code "101") (name "unconnected-(S8-P-Pad3)") (class "Default")
      (node (ref "S8") (pin "3") (pinfunction "P_3") (pintype "passive"))
    )
    (net (code "102") (name "unconnected-(S8-P1-Pad4)") (class "Default")
      (node (ref "S8") (pin "4") (pinfunction "P1_4") (pintype "passive"))
    )
    (net (code "103") (name "unconnected-(S8-S-Pad1)") (class "Default")
      (node (ref "S8") (pin "1") (pinfunction "S_1") (pintype "passive"))
    )
    (net (code "104") (name "unconnected-(S8-S1-Pad2)") (class "Default")
      (node (ref "S8") (pin "2") (pinfunction "S1_2") (pintype "passive"))
    )
    (net (code "105") (name "unconnected-(S9-P-Pad3)") (class "Default")
      (node (ref "S9") (pin "3") (pinfunction "P_3") (pintype "passive"))
    )
    (net (code "106") (name "unconnected-(S9-P1-Pad4)") (class "Default")
      (node (ref "S9") (pin "4") (pinfunction "P1_4") (pintype "passive"))
    )
    (net (code "107") (name "unconnected-(S9-S-Pad1)") (class "Default")
      (node (ref "S9") (pin "1") (pinfunction "S_1") (pintype "passive"))
    )
    (net (code "108") (name "unconnected-(S9-S1-Pad2)") (class "Default")
      (node (ref "S9") (pin "2") (pinfunction "S1_2") (pintype "passive"))
    )
    (net (code "109") (name "unconnected-(S10-P-Pad3)") (class "Default")
      (node (ref "S10") (pin "3") (pinfunction "P_3") (pintype "passive"))
    )
    (net (code "110") (name "unconnected-(S10-P1-Pad4)") (class "Default")
      (node (ref "S10") (pin "4") (pinfunction "P1_4") (pintype "passive"))
    )
    (net (code "111") (name "unconnected-(S10-S-Pad1)") (class "Default")
      (node (ref "S10") (pin "1") (pinfunction "S_1") (pintype "passive"))
    )
    (net (code "112") (name "unconnected-(S10-S1-Pad2)") (class "Default")
      (node (ref "S10") (pin "2") (pinfunction "S1_2") (pintype "passive"))
    )
    (net (code "113") (name "unconnected-(S11-P-Pad3)") (class "Default")
      (node (ref "S11") (pin "3") (pinfunction "P_3") (pintype "passive"))
    )
    (net (code "114") (name "unconnected-(S11-P1-Pad4)") (class "Default")
      (node (ref "S11") (pin "4") (pinfunction "P1_4") (pintype "passive"))
    )
    (net (code "115") (name "unconnected-(S11-S-Pad1)") (class "Default")
      (node (ref "S11") (pin "1") (pinfunction "S_1") (pintype "passive"))
    )
    (net (code "116") (name "unconnected-(S11-S1-Pad2)") (class "Default")
      (node (ref "S11") (pin "2") (pinfunction "S1_2") (pintype "passive"))
    )
    (net (code "117") (name "unconnected-(S12-P-Pad3)") (class "Default")
      (node (ref "S12") (pin "3") (pinfunction "P_3") (pintype "passive"))
    )
    (net (code "118") (name "unconnected-(S12-P1-Pad4)") (class "Default")
      (node (ref "S12") (pin "4") (pinfunction "P1_4") (pintype "passive"))
    )
    (net (code "119") (name "unconnected-(S12-S-Pad1)") (class "Default")
      (node (ref "S12") (pin "1") (pinfunction "S_1") (pintype "passive"))
    )
    (net (code "120") (name "unconnected-(S12-S1-Pad2)") (class "Default")
      (node (ref "S12") (pin "2") (pinfunction "S1_2") (pintype "passive"))
    )
    (net (code "121") (name "unconnected-(S13-P-Pad3)") (class "Default")
      (node (ref "S13") (pin "3") (pinfunction "P_3") (pintype "passive"))
    )
    (net (code "122") (name "unconnected-(S13-P1-Pad4)") (class "Default")
      (node (ref "S13") (pin "4") (pinfunction "P1_4") (pintype "passive"))
    )
    (net (code "123") (name "unconnected-(S13-S-Pad1)") (class "Default")
      (node (ref "S13") (pin "1") (pinfunction "S_1") (pintype "passive"))
    )
    (net (code "124") (name "unconnected-(S13-S1-Pad2)") (class "Default")
      (node (ref "S13") (pin "2") (pinfunction "S1_2") (pintype "passive"))
    )
    (net (code "125") (name "unconnected-(S14-P-Pad3)") (class "Default")
      (node (ref "S14") (pin "3") (pinfunction "P_3") (pintype "passive"))
    )
    (net (code "126") (name "unconnected-(S14-P1-Pad4)") (class "Default")
      (node (ref "S14") (pin "4") (pinfunction "P1_4") (pintype "passive"))
    )
    (net (code "127") (name "unconnected-(S14-S-Pad1)") (class "Default")
      (node (ref "S14") (pin "1") (pinfunction "S_1") (pintype "passive"))
    )
    (net (code "128") (name "unconnected-(S14-S1-Pad2)") (class "Default")
      (node (ref "S14") (pin "2") (pinfunction "S1_2") (pintype "passive"))
    )
    (net (code "129") (name "unconnected-(S15-P-Pad3)") (class "Default")
      (node (ref "S15") (pin "3") (pinfunction "P_3") (pintype "passive"))
    )
    (net (code "130") (name "unconnected-(S15-P1-Pad4)") (class "Default")
      (node (ref "S15") (pin "4") (pinfunction "P1_4") (pintype "passive"))
    )
    (net (code "131") (name "unconnected-(S15-S-Pad1)") (class "Default")
      (node (ref "S15") (pin "1") (pinfunction "S_1") (pintype "passive"))
    )
    (net (code "132") (name "unconnected-(S15-S1-Pad2)") (class "Default")
      (node (ref "S15") (pin "2") (pinfunction "S1_2") (pintype "passive"))
    )
    (net (code "133") (name "unconnected-(S16-P-Pad3)") (class "Default")
      (node (ref "S16") (pin "3") (pinfunction "P_3") (pintype "passive"))
    )
    (net (code "134") (name "unconnected-(S16-P1-Pad4)") (class "Default")
      (node (ref "S16") (pin "4") (pinfunction "P1_4") (pintype "passive"))
    )
    (net (code "135") (name "unconnected-(S16-S-Pad1)") (class "Default")
      (node (ref "S16") (pin "1") (pinfunction "S_1") (pintype "passive"))
    )
    (net (code "136") (name "unconnected-(S16-S1-Pad2)") (class "Default")
      (node (ref "S16") (pin "2") (pinfunction "S1_2") (pintype "passive"))
    )
    (net (code "137") (name "unconnected-(S17-P-Pad3)") (class "Default")
      (node (ref "S17") (pin "3") (pinfunction "P_3") (pintype "passive"))
    )
    (net (code "138") (name "unconnected-(S17-P1-Pad4)") (class "Default")
      (node (ref "S17") (pin "4") (pinfunction "P1_4") (pintype "passive"))
    )
    (net (code "139") (name "unconnected-(S17-S-Pad1)") (class "Default")
      (node (ref "S17") (pin "1") (pinfunction "S_1") (pintype "passive"))
    )
    (net (code "140") (name "unconnected-(S17-S1-Pad2)") (class "Default")
      (node (ref "S17") (pin "2") (pinfunction "S1_2") (pintype "passive"))
    )
    (net (code "141") (name "unconnected-(S18-P-Pad3)") (class "Default")
      (node (ref "S18") (pin "3") (pinfunction "P_3") (pintype "passive"))
    )
    (net (code "142") (name "unconnected-(S18-P1-Pad4)") (class "Default")
      (node (ref "S18") (pin "4") (pinfunction "P1_4") (pintype "passive"))
    )
    (net (code "143") (name "unconnected-(S18-S-Pad1)") (class "Default")
      (node (ref "S18") (pin "1") (pinfunction "S_1") (pintype "passive"))
    )
    (net (code "144") (name "unconnected-(S18-S1-Pad2)") (class "Default")
      (node (ref "S18") (pin "2") (pinfunction "S1_2") (pintype "passive"))
    )
    (net (code "145") (name "unconnected-(S19-P-Pad3)") (class "Default")
      (node (ref "S19") (pin "3") (pinfunction "P_3") (pintype "passive"))
    )
    (net (code "146") (name "unconnected-(S19-P1-Pad4)") (class "Default")
      (node (ref "S19") (pin "4") (pinfunction "P1_4") (pintype "passive"))
    )
    (net (code "147") (name "unconnected-(S19-S-Pad1)") (class "Default")
      (node (ref "S19") (pin "1") (pinfunction "S_1") (pintype "passive"))
    )
    (net (code "148") (name "unconnected-(S19-S1-Pad2)") (class "Default")
      (node (ref "S19") (pin "2") (pinfunction "S1_2") (pintype "passive"))
    )
  )
)
